# ProgrammableGainAmplifier.net
KiCad netlist of a schematic drawn in Altium Designer
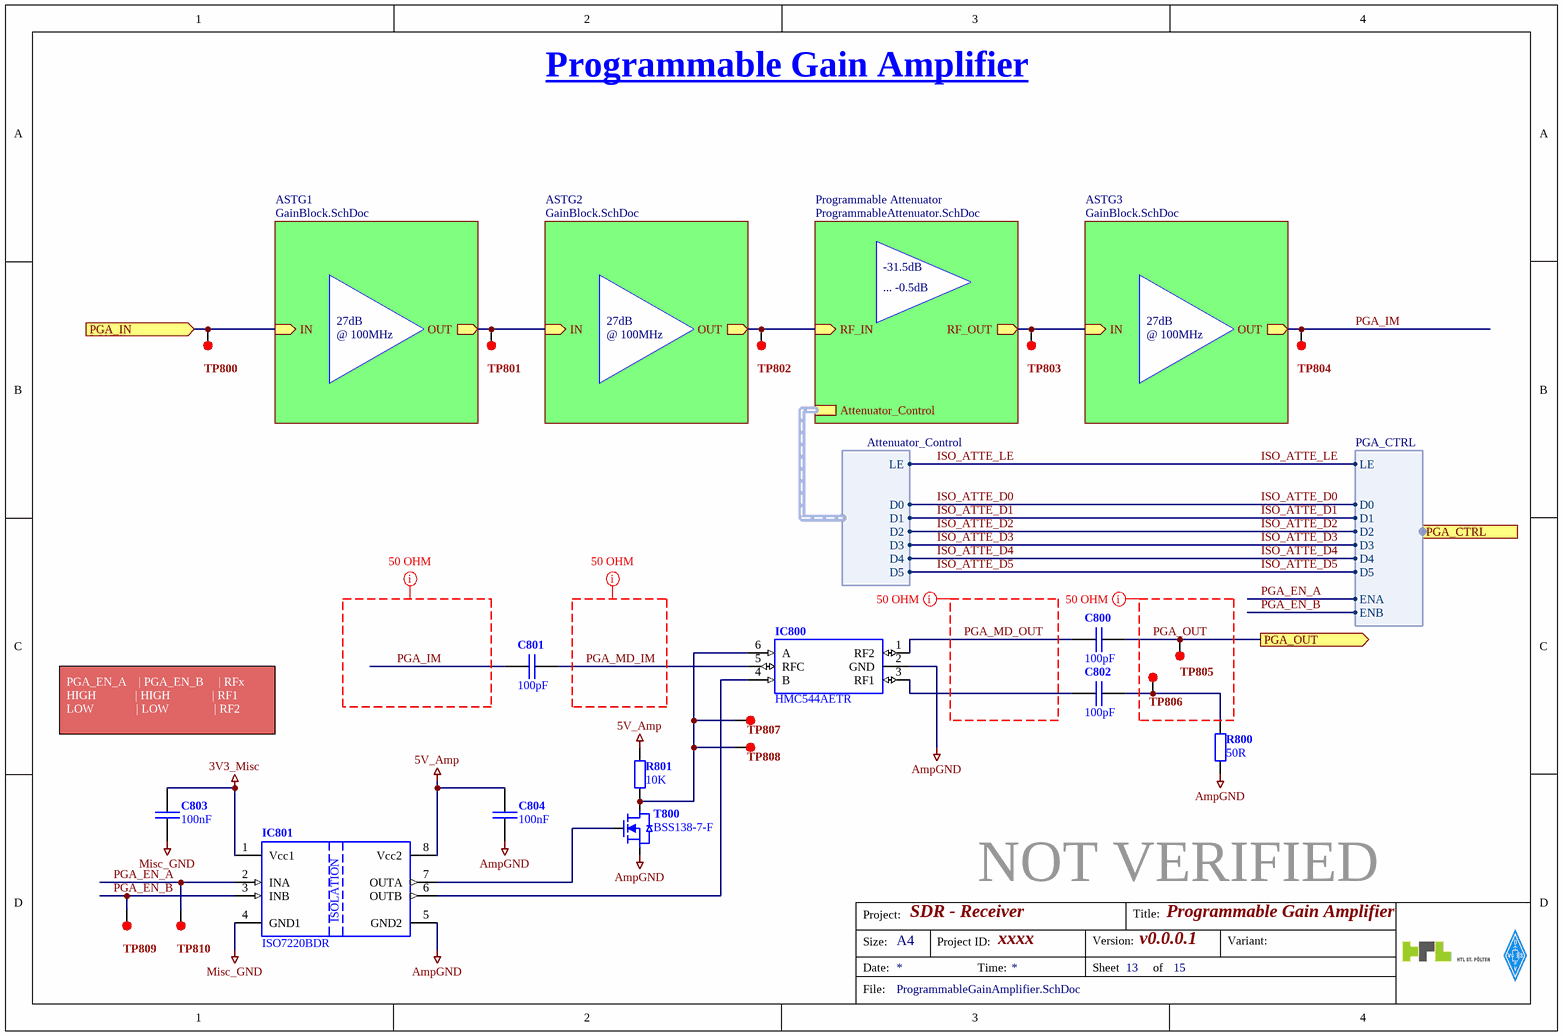
[diagram p0: ProgrammableGainAmplifier.SchDoc]

(export (version "E")
  (design (tool "Eeschema 10.0.6"))
  (components
    (comp (ref "C800")
      (value "100pF")
      (footprint "PrometheusLib:C_0603_N [CAPC1608N IPC]")
      (libsource (lib "PrometheusLib") (part "C_GENERIC"))
    )
    (comp (ref "C801")
      (value "100pF")
      (footprint "PrometheusLib:C_0603_N [CAPC1608N IPC]")
      (libsource (lib "PrometheusLib") (part "C_GENERIC"))
    )
    (comp (ref "C802")
      (value "100pF")
      (footprint "PrometheusLib:C_0603_N [CAPC1608N IPC]")
      (libsource (lib "PrometheusLib") (part "C_GENERIC"))
    )
    (comp (ref "C803")
      (value "100nF")
      (footprint "PrometheusLib:C_0603_N [CAPC1608N IPC]")
      (libsource (lib "PrometheusLib") (part "C_GENERIC"))
    )
    (comp (ref "C804")
      (value "100nF")
      (footprint "PrometheusLib:C_0603_N [CAPC1608N IPC]")
      (libsource (lib "PrometheusLib") (part "C_GENERIC"))
    )
    (comp (ref "IC800")
      (value "HMC544AETR")
      (footprint "TSOP95P280X145-6N IPC")
      (libsource (lib "PrometheusLib") (part "IC_HMC544AETR"))
    )
    (comp (ref "IC801")
      (value "ISO7220BDR")
      (footprint "SOIC127P600X175-8N IPC")
      (description "Dual-Channel Digital Isolator\r\nVcc: 3V3 or 5 V Supply\r\n4 kV ESD protection")
      (libsource (lib "PrometheusLib") (part "IC_ISO7220BDR"))
    )
    (comp (ref "R800")
      (value "50R")
      (footprint "PrometheusLib:R_1206_N [RESC3216N IPC]")
      (libsource (lib "PrometheusLib") (part "R_GENERIC_DIN"))
    )
    (comp (ref "R801")
      (value "10K")
      (footprint "PrometheusLib:R_0603_N [RESC1608N IPC]")
      (libsource (lib "PrometheusLib") (part "R_GENERIC_DIN"))
    )
    (comp (ref "T800")
      (value "BSS138-7-F")
      (footprint "SOT105P235X102-3N IPC")
      (libsource (lib "PrometheusLib") (part "T_NMOS_BSS138-7-F"))
    )
    (comp (ref "TP800")
      (value "TP_GENERIC")
      (footprint "PrometheusLib:TP_0.8_P100T")
      (description "Needle Test Point")
      (libsource (lib "PrometheusLib") (part "TP_GENERIC"))
    )
    (comp (ref "TP801")
      (value "TP_GENERIC")
      (footprint "PrometheusLib:TP_0.8_P100T")
      (description "Needle Test Point")
      (libsource (lib "PrometheusLib") (part "TP_GENERIC"))
    )
    (comp (ref "TP802")
      (value "TP_GENERIC")
      (footprint "PrometheusLib:TP_0.8_P100T")
      (description "Needle Test Point")
      (libsource (lib "PrometheusLib") (part "TP_GENERIC"))
    )
    (comp (ref "TP803")
      (value "TP_GENERIC")
      (footprint "PrometheusLib:TP_0.8_P100T")
      (description "Needle Test Point")
      (libsource (lib "PrometheusLib") (part "TP_GENERIC"))
    )
    (comp (ref "TP804")
      (value "TP_GENERIC")
      (footprint "PrometheusLib:TP_0.8_P100T")
      (description "Needle Test Point")
      (libsource (lib "PrometheusLib") (part "TP_GENERIC"))
    )
    (comp (ref "TP805")
      (value "TP_GENERIC")
      (footprint "PrometheusLib:TP_0.8_P100T")
      (description "Needle Test Point")
      (libsource (lib "PrometheusLib") (part "TP_GENERIC"))
    )
    (comp (ref "TP806")
      (value "TP_GENERIC")
      (footprint "PrometheusLib:TP_0.8_P100T")
      (description "Needle Test Point")
      (libsource (lib "PrometheusLib") (part "TP_GENERIC"))
    )
    (comp (ref "TP807")
      (value "TP_GENERIC")
      (footprint "PrometheusLib:TP_0.8_P100T")
      (description "Needle Test Point")
      (libsource (lib "PrometheusLib") (part "TP_GENERIC"))
    )
    (comp (ref "TP808")
      (value "TP_GENERIC")
      (footprint "PrometheusLib:TP_0.8_P100T")
      (description "Needle Test Point")
      (libsource (lib "PrometheusLib") (part "TP_GENERIC"))
    )
    (comp (ref "TP809")
      (value "TP_GENERIC")
      (footprint "PrometheusLib:TP_0.8_P100T")
      (description "Needle Test Point")
      (libsource (lib "PrometheusLib") (part "TP_GENERIC"))
    )
    (comp (ref "TP810")
      (value "TP_GENERIC")
      (footprint "PrometheusLib:TP_0.8_P100T")
      (description "Needle Test Point")
      (libsource (lib "PrometheusLib") (part "TP_GENERIC"))
    )
  )
  (nets
    (net (code "10") (name "/OUT") (class "Default")
      (node (ref "TP801") (pin "1") (pinfunction "1_1") (pintype "passive"))
    )
    (net (code "11") (name "/OUT_1") (class "Default")
      (node (ref "TP802") (pin "1") (pinfunction "1_1") (pintype "passive"))
    )
    (net (code "12") (name "/PGA_EN_A") (class "Default")
      (node (ref "IC801") (pin "2") (pinfunction "INA_2") (pintype "input"))
      (node (ref "TP810") (pin "1") (pinfunction "1_1") (pintype "passive"))
    )
    (net (code "13") (name "/PGA_EN_B") (class "Default")
      (node (ref "IC801") (pin "3") (pinfunction "INB_3") (pintype "input"))
      (node (ref "TP809") (pin "1") (pinfunction "1_1") (pintype "passive"))
    )
    (net (code "14") (name "/PGA_IM") (class "Default")
      (node (ref "C801") (pin "1") (pintype "passive"))
      (node (ref "TP804") (pin "1") (pinfunction "1_1") (pintype "passive"))
    )
    (net (code "15") (name "/PGA_IN") (class "Default")
      (node (ref "TP800") (pin "1") (pinfunction "1_1") (pintype "passive"))
    )
    (net (code "16") (name "/PGA_MD_IM") (class "Default")
      (node (ref "C801") (pin "2") (pintype "passive"))
      (node (ref "IC800") (pin "5") (pinfunction "RFC_5") (pintype "bidirectional"))
    )
    (net (code "17") (name "/PGA_MD_OUT") (class "Default")
      (node (ref "C800") (pin "1") (pintype "passive"))
      (node (ref "IC800") (pin "1") (pinfunction "RF2_1") (pintype "bidirectional"))
    )
    (net (code "18") (name "/PGA_OUT") (class "Default")
      (node (ref "C800") (pin "2") (pintype "passive"))
      (node (ref "TP805") (pin "1") (pinfunction "1_1") (pintype "passive"))
    )
    (net (code "19") (name "/RF_OUT") (class "Default")
      (node (ref "TP803") (pin "1") (pinfunction "1_1") (pintype "passive"))
    )
    (net (code "22") (name "3V3_Misc") (class "Default")
      (node (ref "C803") (pin "1") (pintype "passive"))
      (node (ref "IC801") (pin "1") (pinfunction "Vcc1_1") (pintype "passive"))
    )
    (net (code "23") (name "5V_Amp") (class "Default")
      (node (ref "C804") (pin "1") (pintype "passive"))
      (node (ref "IC801") (pin "8") (pinfunction "Vcc2_8") (pintype "passive"))
      (node (ref "R801") (pin "2") (pinfunction "2_2") (pintype "passive"))
    )
    (net (code "24") (name "AmpGND") (class "Default")
      (node (ref "C804") (pin "2") (pintype "passive"))
      (node (ref "IC800") (pin "2") (pinfunction "GND_2") (pintype "passive"))
      (node (ref "IC801") (pin "5") (pinfunction "GND2_5") (pintype "passive"))
      (node (ref "R800") (pin "1") (pinfunction "1_1") (pintype "passive"))
      (node (ref "T800") (pin "S") (pinfunction "S_S") (pintype "passive"))
    )
    (net (code "25") (name "Misc_GND") (class "Default")
      (node (ref "C803") (pin "2") (pintype "passive"))
      (node (ref "IC801") (pin "4") (pinfunction "GND1_4") (pintype "passive"))
    )
    (net (code "26") (name "Net-(C802-Pad2)") (class "Default")
      (node (ref "C802") (pin "2") (pintype "passive"))
      (node (ref "R800") (pin "2") (pinfunction "2_2") (pintype "passive"))
      (node (ref "TP806") (pin "1") (pinfunction "1_1") (pintype "passive"))
    )
    (net (code "27") (name "Net-(IC800-A)") (class "Default")
      (node (ref "IC800") (pin "6") (pinfunction "A_6") (pintype "input"))
      (node (ref "R801") (pin "1") (pinfunction "1_1") (pintype "passive"))
      (node (ref "T800") (pin "D") (pinfunction "D_D") (pintype "passive"))
      (node (ref "TP807") (pin "1") (pinfunction "1_1") (pintype "passive"))
      (node (ref "TP808") (pin "1") (pinfunction "1_1") (pintype "passive"))
    )
    (net (code "28") (name "Net-(IC800-B)") (class "Default")
      (node (ref "IC800") (pin "4") (pinfunction "B_4") (pintype "input"))
      (node (ref "IC801") (pin "6") (pinfunction "OUTB_6") (pintype "output"))
    )
    (net (code "29") (name "Net-(IC800-RF1)") (class "Default")
      (node (ref "C802") (pin "1") (pintype "passive"))
      (node (ref "IC800") (pin "3") (pinfunction "RF1_3") (pintype "bidirectional"))
    )
    (net (code "30") (name "Net-(IC801-OUTA)") (class "Default")
      (node (ref "IC801") (pin "7") (pinfunction "OUTA_7") (pintype "output"))
      (node (ref "T800") (pin "G") (pinfunction "G_G") (pintype "passive"))
    )
  )
)
